# mainboard.net
KiCad netlist of a schematic drawn in EAGLE
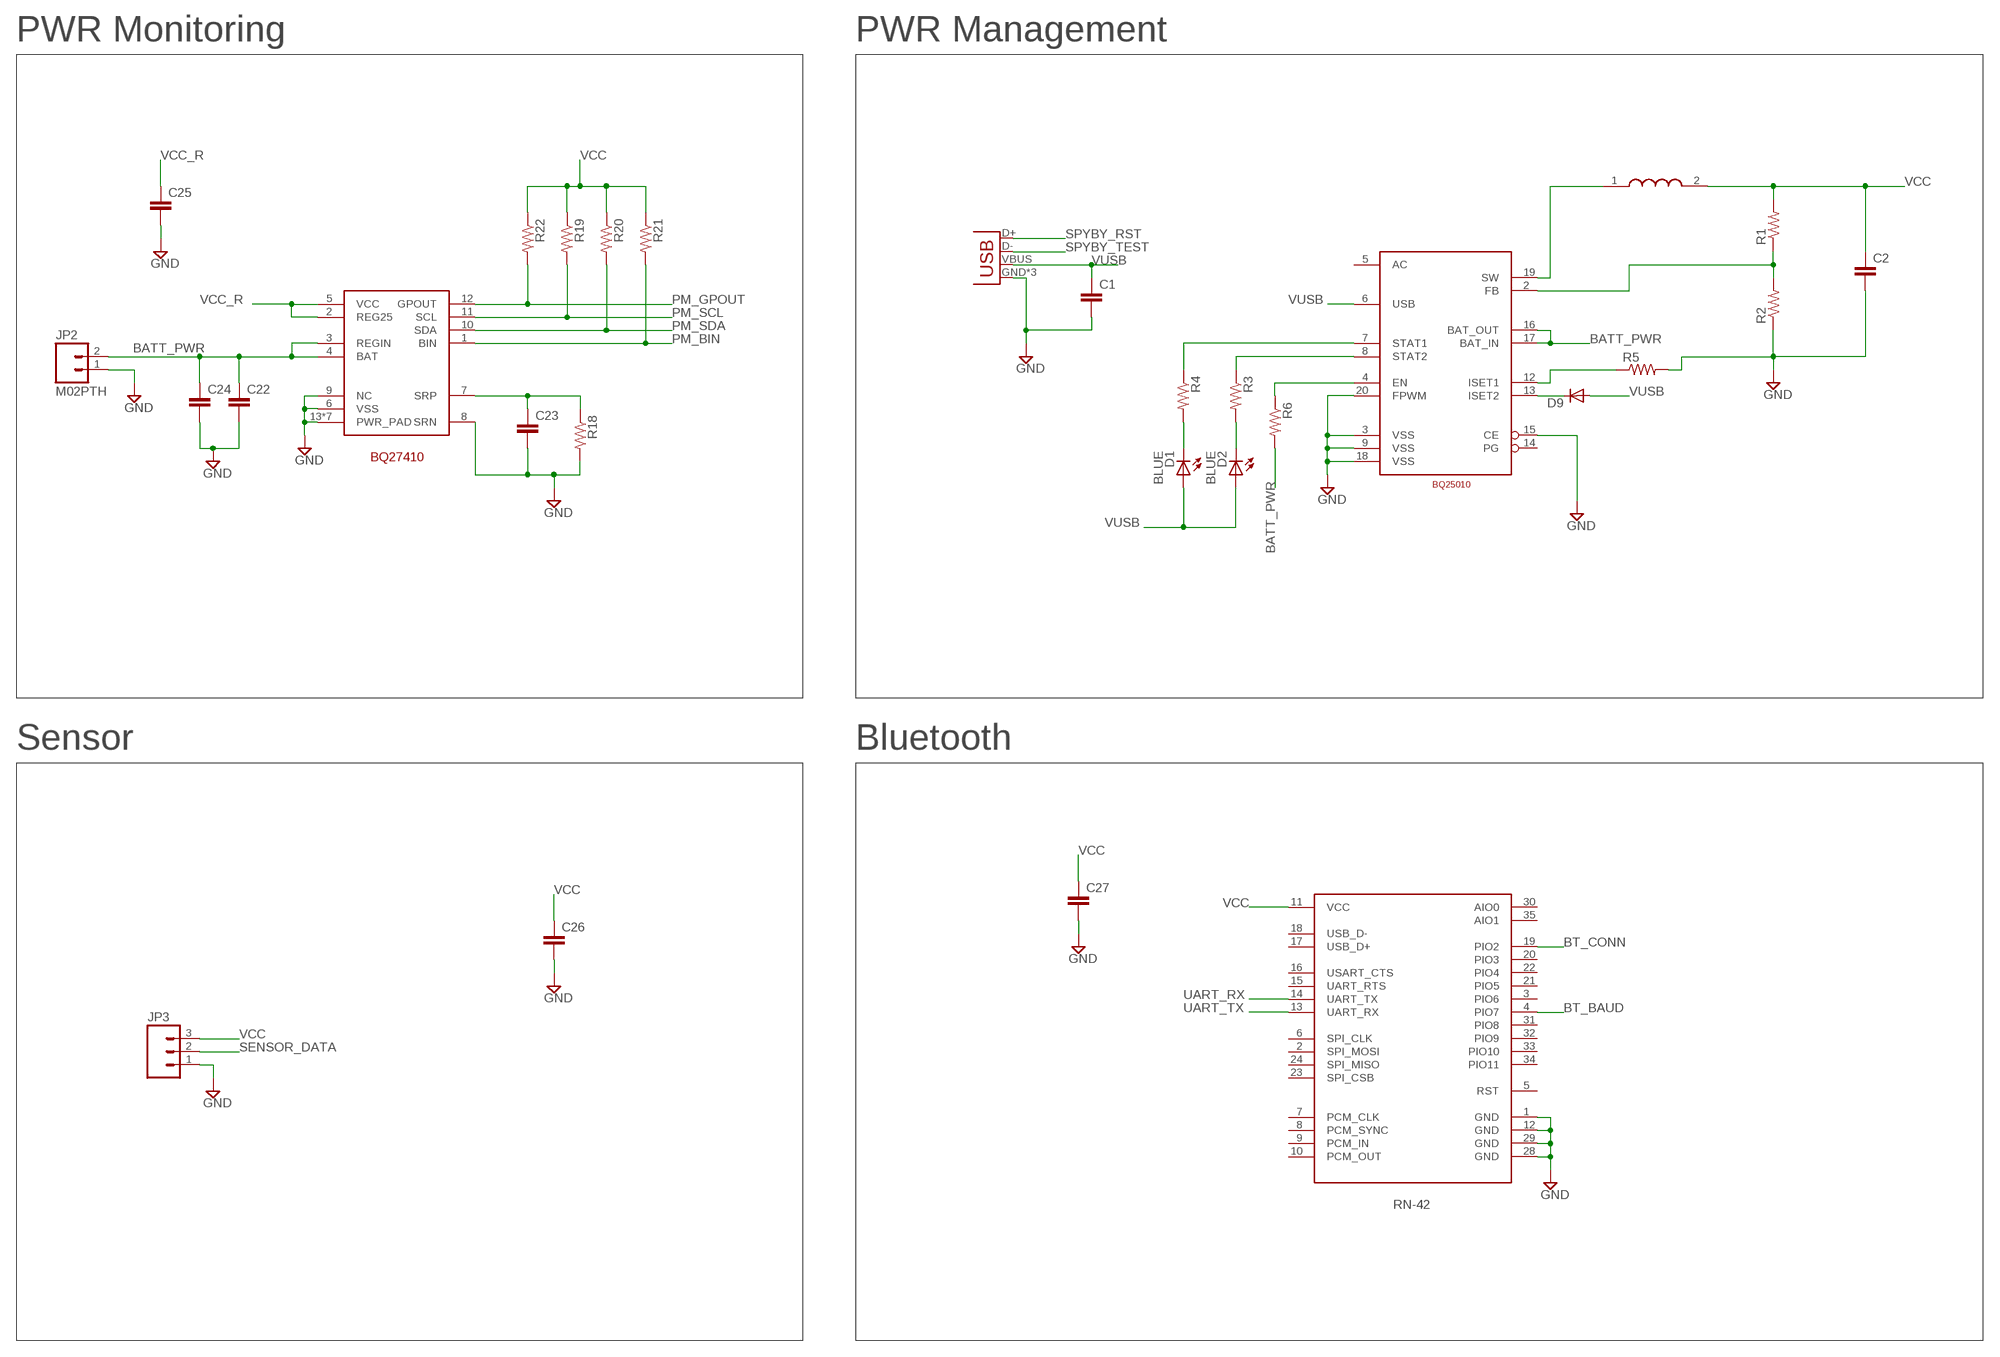
[diagram p0: schematic, sheet 1, part 1 of 2]
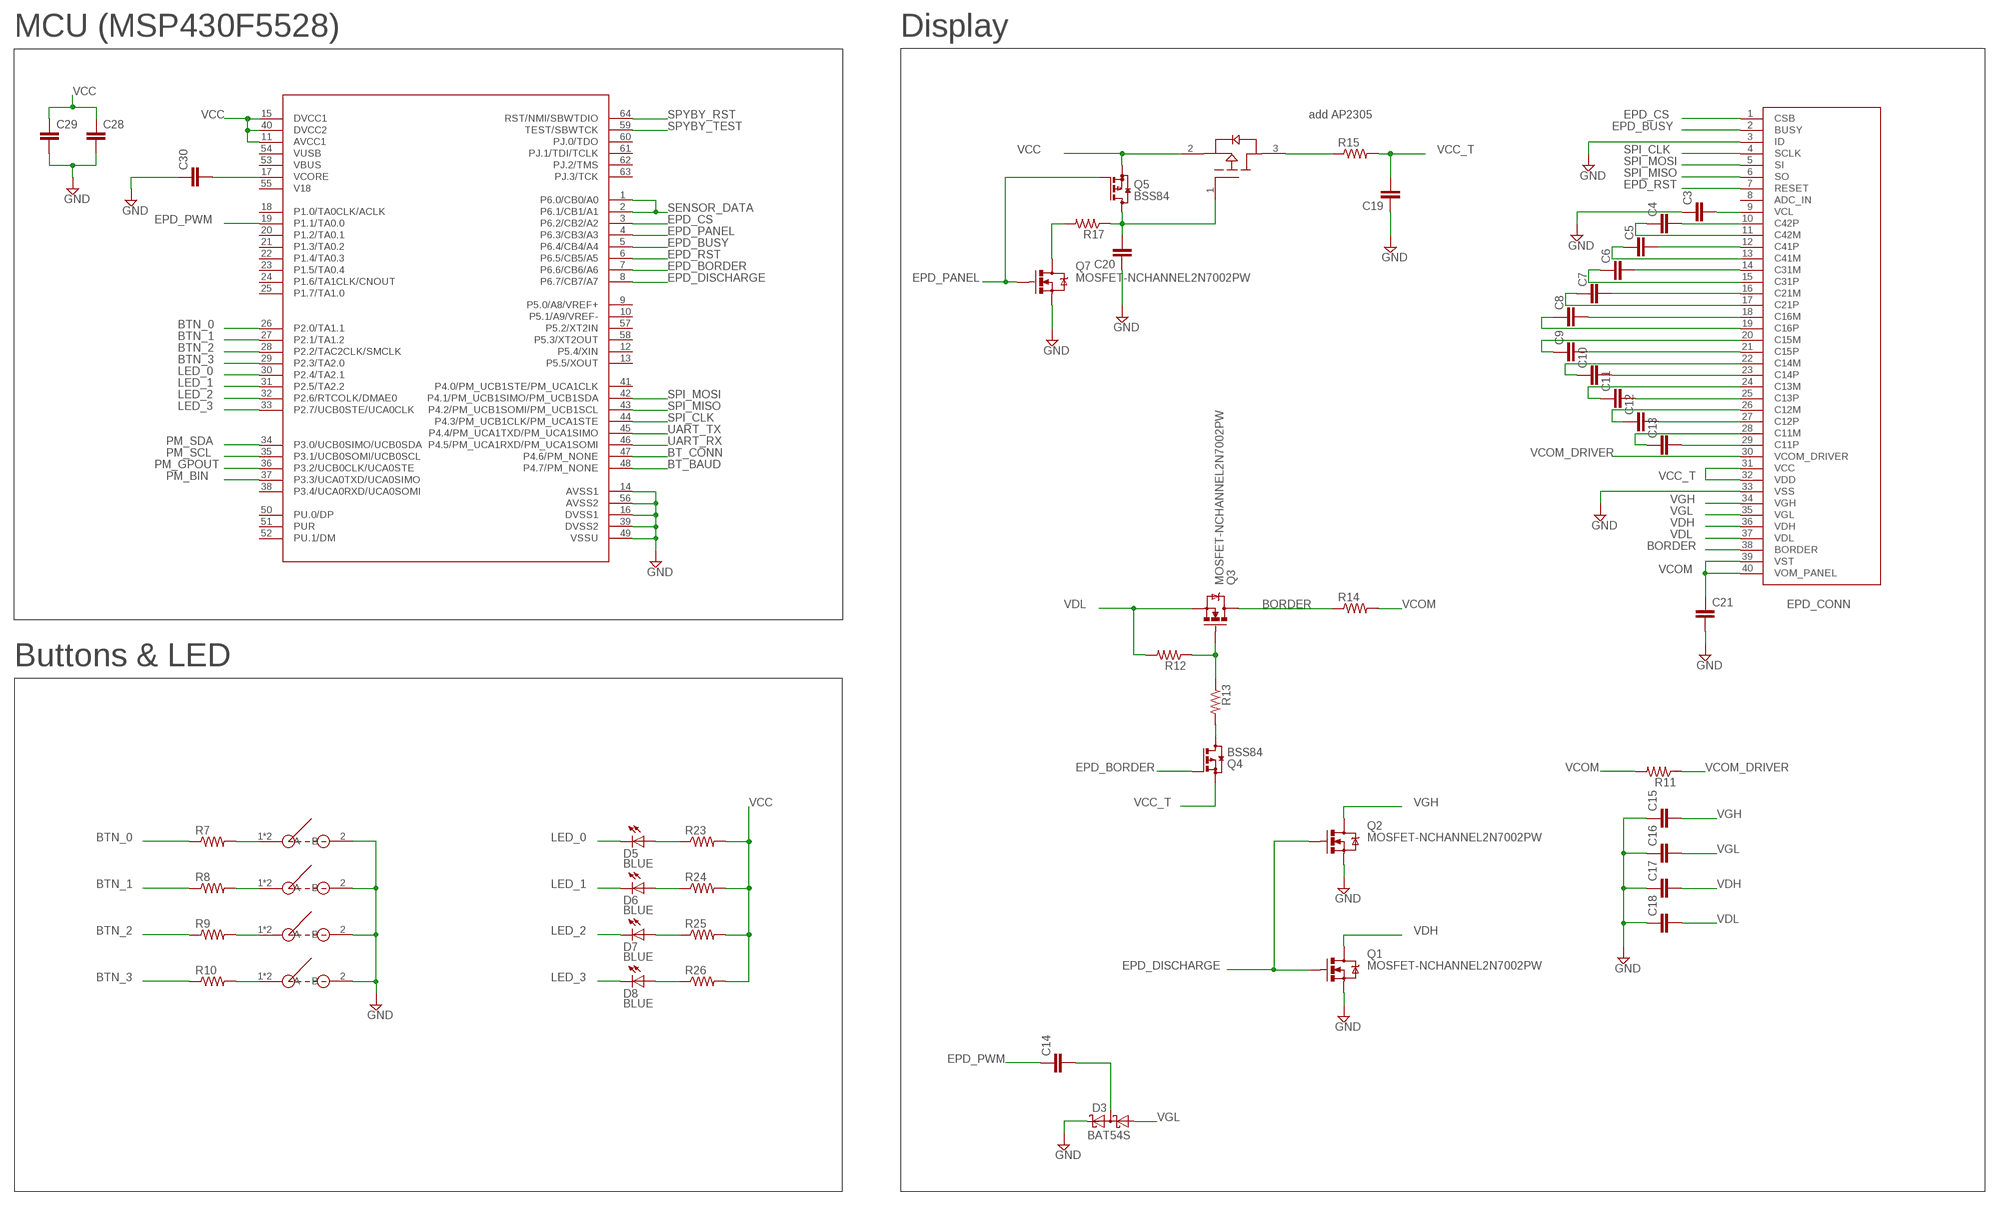
[diagram p1: schematic, sheet 1, part 2 of 2]

(export (version "E")
  (design (tool "Eeschema 10.0.6"))
  (components
    (comp (ref "C1")
      (value "CAP0402-CAP")
      (footprint "eagle-import:0402-CAP")
      (libsource (lib "eagle-import") (part "CAP0402-CAP"))
    )
    (comp (ref "C2")
      (value "CAP0402-CAP")
      (footprint "eagle-import:0402-CAP")
      (libsource (lib "eagle-import") (part "CAP0402-CAP"))
    )
    (comp (ref "C3")
      (value "CAP0402-CAP")
      (footprint "eagle-import:0402-CAP")
      (libsource (lib "eagle-import") (part "CAP0402-CAP"))
    )
    (comp (ref "C4")
      (value "CAP0402-CAP")
      (footprint "eagle-import:0402-CAP")
      (libsource (lib "eagle-import") (part "CAP0402-CAP"))
    )
    (comp (ref "C5")
      (value "CAP0402-CAP")
      (footprint "eagle-import:0402-CAP")
      (libsource (lib "eagle-import") (part "CAP0402-CAP"))
    )
    (comp (ref "C6")
      (value "CAP0402-CAP")
      (footprint "eagle-import:0402-CAP")
      (libsource (lib "eagle-import") (part "CAP0402-CAP"))
    )
    (comp (ref "C7")
      (value "CAP0402-CAP")
      (footprint "eagle-import:0402-CAP")
      (libsource (lib "eagle-import") (part "CAP0402-CAP"))
    )
    (comp (ref "C8")
      (value "CAP0402-CAP")
      (footprint "eagle-import:0402-CAP")
      (libsource (lib "eagle-import") (part "CAP0402-CAP"))
    )
    (comp (ref "C9")
      (value "CAP0402-CAP")
      (footprint "eagle-import:0402-CAP")
      (libsource (lib "eagle-import") (part "CAP0402-CAP"))
    )
    (comp (ref "C10")
      (value "CAP0402-CAP")
      (footprint "eagle-import:0402-CAP")
      (libsource (lib "eagle-import") (part "CAP0402-CAP"))
    )
    (comp (ref "C11")
      (value "CAP0402-CAP")
      (footprint "eagle-import:0402-CAP")
      (libsource (lib "eagle-import") (part "CAP0402-CAP"))
    )
    (comp (ref "C12")
      (value "CAP0402-CAP")
      (footprint "eagle-import:0402-CAP")
      (libsource (lib "eagle-import") (part "CAP0402-CAP"))
    )
    (comp (ref "C13")
      (value "CAP0402-CAP")
      (footprint "eagle-import:0402-CAP")
      (libsource (lib "eagle-import") (part "CAP0402-CAP"))
    )
    (comp (ref "C14")
      (value "CAP0402-CAP")
      (footprint "eagle-import:0402-CAP")
      (libsource (lib "eagle-import") (part "CAP0402-CAP"))
    )
    (comp (ref "C15")
      (value "CAP0402-CAP")
      (footprint "eagle-import:0402-CAP")
      (libsource (lib "eagle-import") (part "CAP0402-CAP"))
    )
    (comp (ref "C16")
      (value "CAP0402-CAP")
      (footprint "eagle-import:0402-CAP")
      (libsource (lib "eagle-import") (part "CAP0402-CAP"))
    )
    (comp (ref "C17")
      (value "CAP0402-CAP")
      (footprint "eagle-import:0402-CAP")
      (libsource (lib "eagle-import") (part "CAP0402-CAP"))
    )
    (comp (ref "C18")
      (value "CAP0402-CAP")
      (footprint "eagle-import:0402-CAP")
      (libsource (lib "eagle-import") (part "CAP0402-CAP"))
    )
    (comp (ref "C19")
      (value "CAP0402-CAP")
      (footprint "eagle-import:0402-CAP")
      (libsource (lib "eagle-import") (part "CAP0402-CAP"))
    )
    (comp (ref "C20")
      (value "CAP0402-CAP")
      (footprint "eagle-import:0402-CAP")
      (libsource (lib "eagle-import") (part "CAP0402-CAP"))
    )
    (comp (ref "C21")
      (value "CAP0402-CAP")
      (footprint "eagle-import:0402-CAP")
      (libsource (lib "eagle-import") (part "CAP0402-CAP"))
    )
    (comp (ref "C22")
      (value "CAP0402-CAP")
      (footprint "eagle-import:0402-CAP")
      (libsource (lib "eagle-import") (part "CAP0402-CAP"))
    )
    (comp (ref "C23")
      (value "CAP0402-CAP")
      (footprint "eagle-import:0402-CAP")
      (libsource (lib "eagle-import") (part "CAP0402-CAP"))
    )
    (comp (ref "C24")
      (value "CAP0402-CAP")
      (footprint "eagle-import:0402-CAP")
      (libsource (lib "eagle-import") (part "CAP0402-CAP"))
    )
    (comp (ref "C25")
      (value "CAP0402-CAP")
      (footprint "eagle-import:0402-CAP")
      (libsource (lib "eagle-import") (part "CAP0402-CAP"))
    )
    (comp (ref "C26")
      (value "CAP0402-CAP")
      (footprint "eagle-import:0402-CAP")
      (libsource (lib "eagle-import") (part "CAP0402-CAP"))
    )
    (comp (ref "C27")
      (value "CAP0402-CAP")
      (footprint "eagle-import:0402-CAP")
      (libsource (lib "eagle-import") (part "CAP0402-CAP"))
    )
    (comp (ref "C28")
      (value "CAP0402-CAP")
      (footprint "eagle-import:0402-CAP")
      (libsource (lib "eagle-import") (part "CAP0402-CAP"))
    )
    (comp (ref "C29")
      (value "CAP0402-CAP")
      (footprint "eagle-import:0402-CAP")
      (libsource (lib "eagle-import") (part "CAP0402-CAP"))
    )
    (comp (ref "C30")
      (value "CAP0402-CAP")
      (footprint "eagle-import:0402-CAP")
      (libsource (lib "eagle-import") (part "CAP0402-CAP"))
    )
    (comp (ref "D1")
      (value "BLUE")
      (footprint "eagle-import:LED-0603")
      (libsource (lib "eagle-import") (part "LED-BLUE0603"))
    )
    (comp (ref "D2")
      (value "BLUE")
      (footprint "eagle-import:LED-0603")
      (libsource (lib "eagle-import") (part "LED-BLUE0603"))
    )
    (comp (ref "D3")
      (value "BAT54S")
      (footprint "eagle-import:SOT23")
      (libsource (lib "eagle-import") (part "BAT54S"))
    )
    (comp (ref "D5")
      (value "BLUE")
      (footprint "eagle-import:LED-0603")
      (libsource (lib "eagle-import") (part "LED-BLUE0603"))
    )
    (comp (ref "D6")
      (value "BLUE")
      (footprint "eagle-import:LED-0603")
      (libsource (lib "eagle-import") (part "LED-BLUE0603"))
    )
    (comp (ref "D7")
      (value "BLUE")
      (footprint "eagle-import:LED-0603")
      (libsource (lib "eagle-import") (part "LED-BLUE0603"))
    )
    (comp (ref "D8")
      (value "BLUE")
      (footprint "eagle-import:LED-0603")
      (libsource (lib "eagle-import") (part "LED-BLUE0603"))
    )
    (comp (ref "D9")
      (value "DIODESOD523")
      (footprint "eagle-import:SOD523")
      (libsource (lib "eagle-import") (part "DIODESOD523"))
    )
    (comp (ref "JP1")
      (value "USB-MICROB")
      (footprint "eagle-import:USB-MICROB")
      (libsource (lib "eagle-import") (part "USB-MICROB"))
    )
    (comp (ref "JP2")
      (value "M02PTH")
      (footprint "eagle-import:1X02")
      (libsource (lib "eagle-import") (part "M02PTH"))
    )
    (comp (ref "JP3")
      (value "M03PTH")
      (footprint "eagle-import:1X03")
      (libsource (lib "eagle-import") (part "M03PTH"))
    )
    (comp (ref "Q1")
      (value "MOSFET-NCHANNEL2N7002PW")
      (footprint "eagle-import:SOT323")
      (libsource (lib "eagle-import") (part "MOSFET-NCHANNEL2N7002PW"))
    )
    (comp (ref "Q2")
      (value "MOSFET-NCHANNEL2N7002PW")
      (footprint "eagle-import:SOT323")
      (libsource (lib "eagle-import") (part "MOSFET-NCHANNEL2N7002PW"))
    )
    (comp (ref "Q3")
      (value "MOSFET-NCHANNEL2N7002PW")
      (footprint "eagle-import:SOT323")
      (libsource (lib "eagle-import") (part "MOSFET-NCHANNEL2N7002PW"))
    )
    (comp (ref "Q4")
      (value "BSS84")
      (footprint "eagle-import:SOT23")
      (libsource (lib "eagle-import") (part "BSS84"))
    )
    (comp (ref "Q5")
      (value "BSS84")
      (footprint "eagle-import:SOT23")
      (libsource (lib "eagle-import") (part "BSS84"))
    )
    (comp (ref "Q7")
      (value "MOSFET-NCHANNEL2N7002PW")
      (footprint "eagle-import:SOT323")
      (libsource (lib "eagle-import") (part "MOSFET-NCHANNEL2N7002PW"))
    )
    (comp (ref "R1")
      (value "RESISTOR0402-RES")
      (footprint "eagle-import:0402-RES")
      (libsource (lib "eagle-import") (part "RESISTOR0402-RES"))
    )
    (comp (ref "R2")
      (value "RESISTOR0402-RES")
      (footprint "eagle-import:0402-RES")
      (libsource (lib "eagle-import") (part "RESISTOR0402-RES"))
    )
    (comp (ref "R3")
      (value "RESISTOR0402-RES")
      (footprint "eagle-import:0402-RES")
      (libsource (lib "eagle-import") (part "RESISTOR0402-RES"))
    )
    (comp (ref "R4")
      (value "RESISTOR0402-RES")
      (footprint "eagle-import:0402-RES")
      (libsource (lib "eagle-import") (part "RESISTOR0402-RES"))
    )
    (comp (ref "R5")
      (value "RESISTOR0402-RES")
      (footprint "eagle-import:0402-RES")
      (libsource (lib "eagle-import") (part "RESISTOR0402-RES"))
    )
    (comp (ref "R6")
      (value "RESISTOR0402-RES")
      (footprint "eagle-import:0402-RES")
      (libsource (lib "eagle-import") (part "RESISTOR0402-RES"))
    )
    (comp (ref "R7")
      (value "RESISTOR0402-RES")
      (footprint "eagle-import:0402-RES")
      (libsource (lib "eagle-import") (part "RESISTOR0402-RES"))
    )
    (comp (ref "R8")
      (value "RESISTOR0402-RES")
      (footprint "eagle-import:0402-RES")
      (libsource (lib "eagle-import") (part "RESISTOR0402-RES"))
    )
    (comp (ref "R9")
      (value "RESISTOR0402-RES")
      (footprint "eagle-import:0402-RES")
      (libsource (lib "eagle-import") (part "RESISTOR0402-RES"))
    )
    (comp (ref "R10")
      (value "RESISTOR0402-RES")
      (footprint "eagle-import:0402-RES")
      (libsource (lib "eagle-import") (part "RESISTOR0402-RES"))
    )
    (comp (ref "R11")
      (value "RESISTOR0402-RES")
      (footprint "eagle-import:0402-RES")
      (libsource (lib "eagle-import") (part "RESISTOR0402-RES"))
    )
    (comp (ref "R12")
      (value "RESISTOR0402-RES")
      (footprint "eagle-import:0402-RES")
      (libsource (lib "eagle-import") (part "RESISTOR0402-RES"))
    )
    (comp (ref "R13")
      (value "RESISTOR0402-RES")
      (footprint "eagle-import:0402-RES")
      (libsource (lib "eagle-import") (part "RESISTOR0402-RES"))
    )
    (comp (ref "R14")
      (value "RESISTOR0402-RES")
      (footprint "eagle-import:0402-RES")
      (libsource (lib "eagle-import") (part "RESISTOR0402-RES"))
    )
    (comp (ref "R15")
      (value "RESISTOR0402-RES")
      (footprint "eagle-import:0402-RES")
      (libsource (lib "eagle-import") (part "RESISTOR0402-RES"))
    )
    (comp (ref "R17")
      (value "RESISTOR0402-RES")
      (footprint "eagle-import:0402-RES")
      (libsource (lib "eagle-import") (part "RESISTOR0402-RES"))
    )
    (comp (ref "R18")
      (value "RESISTOR0402-RES")
      (footprint "eagle-import:0402-RES")
      (libsource (lib "eagle-import") (part "RESISTOR0402-RES"))
    )
    (comp (ref "R19")
      (value "RESISTOR0402-RES")
      (footprint "eagle-import:0402-RES")
      (libsource (lib "eagle-import") (part "RESISTOR0402-RES"))
    )
    (comp (ref "R20")
      (value "RESISTOR0402-RES")
      (footprint "eagle-import:0402-RES")
      (libsource (lib "eagle-import") (part "RESISTOR0402-RES"))
    )
    (comp (ref "R21")
      (value "RESISTOR0402-RES")
      (footprint "eagle-import:0402-RES")
      (libsource (lib "eagle-import") (part "RESISTOR0402-RES"))
    )
    (comp (ref "R22")
      (value "RESISTOR0402-RES")
      (footprint "eagle-import:0402-RES")
      (libsource (lib "eagle-import") (part "RESISTOR0402-RES"))
    )
    (comp (ref "R23")
      (value "RESISTOR0402-RES")
      (footprint "eagle-import:0402-RES")
      (libsource (lib "eagle-import") (part "RESISTOR0402-RES"))
    )
    (comp (ref "R24")
      (value "RESISTOR0402-RES")
      (footprint "eagle-import:0402-RES")
      (libsource (lib "eagle-import") (part "RESISTOR0402-RES"))
    )
    (comp (ref "R25")
      (value "RESISTOR0402-RES")
      (footprint "eagle-import:0402-RES")
      (libsource (lib "eagle-import") (part "RESISTOR0402-RES"))
    )
    (comp (ref "R26")
      (value "RESISTOR0402-RES")
      (footprint "eagle-import:0402-RES")
      (libsource (lib "eagle-import") (part "RESISTOR0402-RES"))
    )
    (comp (ref "U$1")
      (value "MSP430F5528")
      (footprint "eagle-import:VQFN_RGC_64PIN")
      (libsource (lib "eagle-import") (part "MSP430F5528"))
    )
    (comp (ref "U$2")
      (value "RN-42")
      (footprint "eagle-import:RN-42")
      (libsource (lib "eagle-import") (part "RN-42"))
    )
    (comp (ref "U$3")
      (value "BQ25010")
      (footprint "eagle-import:VQFN_RHL_20PIN")
      (libsource (lib "eagle-import") (part "BQ25010"))
    )
    (comp (ref "U$4")
      (value "EVP-AEDB2A")
      (footprint "eagle-import:EVP-AEDB2A")
      (libsource (lib "eagle-import") (part "EVP-AEDB2A"))
    )
    (comp (ref "U$5")
      (value "EVP-AEDB2A")
      (footprint "eagle-import:EVP-AEDB2A")
      (libsource (lib "eagle-import") (part "EVP-AEDB2A"))
    )
    (comp (ref "U$6")
      (value "EVP-AEDB2A")
      (footprint "eagle-import:EVP-AEDB2A")
      (libsource (lib "eagle-import") (part "EVP-AEDB2A"))
    )
    (comp (ref "U$7")
      (value "EVP-AEDB2A")
      (footprint "eagle-import:EVP-AEDB2A")
      (libsource (lib "eagle-import") (part "EVP-AEDB2A"))
    )
    (comp (ref "U$8")
      (value "FH12-40S-0.5SH")
      (footprint "eagle-import:FH12-40S-0.5SH")
      (libsource (lib "eagle-import") (part "FH12-40S-0.5SH"))
    )
    (comp (ref "U$9")
      (value "BQ27410")
      (footprint "eagle-import:SON_DRZ_12PIN")
      (libsource (lib "eagle-import") (part "BQ27410"))
    )
    (comp (ref "U$10")
      (value "DMG2305UX")
      (footprint "eagle-import:SOT23")
      (libsource (lib "eagle-import") (part "DMG2305UX"))
    )
    (comp (ref "U$11")
      (value "ASPI-0428S-100M-T")
      (footprint "eagle-import:ASPI_0428S-100M-T")
      (libsource (lib "eagle-import") (part "ASPI-0428S-100M-T"))
    )
  )
  (nets
    (net (code "1") (name "/BATT_PWR") (class "Default")
      (node (ref "C22") (pin "1") (pinfunction "1_1") (pintype "passive"))
      (node (ref "C24") (pin "1") (pinfunction "1_1") (pintype "passive"))
      (node (ref "JP2") (pin "2") (pinfunction "2_2") (pintype "passive"))
      (node (ref "R6") (pin "2") (pinfunction "2_2") (pintype "passive"))
      (node (ref "U$3") (pin "16") (pinfunction "BAT_OUT_16") (pintype "bidirectional"))
      (node (ref "U$3") (pin "17") (pinfunction "BAT_IN_17") (pintype "bidirectional"))
      (node (ref "U$9") (pin "3") (pinfunction "REGIN_3") (pintype "bidirectional"))
      (node (ref "U$9") (pin "4") (pinfunction "BAT_4") (pintype "bidirectional"))
    )
    (net (code "2") (name "/BORDER") (class "Default")
      (node (ref "Q3") (pin "3") (pinfunction "D_3") (pintype "passive"))
      (node (ref "R14") (pin "1") (pinfunction "1_1") (pintype "passive"))
      (node (ref "U$8") (pin "38") (pinfunction "BORDER_38") (pintype "bidirectional"))
    )
    (net (code "3") (name "/BTN_0") (class "Default")
      (node (ref "R7") (pin "1") (pinfunction "1_1") (pintype "passive"))
      (node (ref "U$1") (pin "26") (pinfunction "P2.0/TA1.1_26") (pintype "bidirectional"))
    )
    (net (code "4") (name "/BTN_1") (class "Default")
      (node (ref "R8") (pin "1") (pinfunction "1_1") (pintype "passive"))
      (node (ref "U$1") (pin "27") (pinfunction "P2.1/TA1.2_27") (pintype "bidirectional"))
    )
    (net (code "5") (name "/BTN_2") (class "Default")
      (node (ref "R9") (pin "1") (pinfunction "1_1") (pintype "passive"))
      (node (ref "U$1") (pin "28") (pinfunction "P2.2/TAC2CLK/SMCLK_28") (pintype "bidirectional"))
    )
    (net (code "6") (name "/BTN_3") (class "Default")
      (node (ref "R10") (pin "1") (pinfunction "1_1") (pintype "passive"))
      (node (ref "U$1") (pin "29") (pinfunction "P2.3/TA2.0_29") (pintype "bidirectional"))
    )
    (net (code "7") (name "/BT_BAUD") (class "Default")
      (node (ref "U$1") (pin "48") (pinfunction "P4.7/PM_NONE_48") (pintype "bidirectional"))
      (node (ref "U$2") (pin "4") (pinfunction "PIO7_4") (pintype "bidirectional"))
    )
    (net (code "8") (name "/BT_CONN") (class "Default")
      (node (ref "U$1") (pin "47") (pinfunction "P4.6/PM_NONE_47") (pintype "bidirectional"))
      (node (ref "U$2") (pin "19") (pinfunction "PIO2_19") (pintype "bidirectional"))
    )
    (net (code "9") (name "/EPD_BORDER") (class "Default")
      (node (ref "Q4") (pin "1") (pinfunction "G_1") (pintype "passive"))
      (node (ref "U$1") (pin "7") (pinfunction "P6.6/CB6/A6_7") (pintype "bidirectional"))
    )
    (net (code "10") (name "/EPD_BUSY") (class "Default")
      (node (ref "U$1") (pin "5") (pinfunction "P6.4/CB4/A4_5") (pintype "bidirectional"))
      (node (ref "U$8") (pin "2") (pinfunction "BUSY_2") (pintype "bidirectional"))
    )
    (net (code "11") (name "/EPD_CS") (class "Default")
      (node (ref "U$1") (pin "3") (pinfunction "P6.2/CB2/A2_3") (pintype "bidirectional"))
      (node (ref "U$8") (pin "1") (pinfunction "CSB_1") (pintype "bidirectional"))
    )
    (net (code "12") (name "/EPD_DISCHARGE") (class "Default")
      (node (ref "Q1") (pin "1") (pinfunction "G_1") (pintype "passive"))
      (node (ref "Q2") (pin "1") (pinfunction "G_1") (pintype "passive"))
      (node (ref "U$1") (pin "8") (pinfunction "P6.7/CB7/A7_8") (pintype "bidirectional"))
    )
    (net (code "13") (name "/EPD_PANEL") (class "Default")
      (node (ref "Q5") (pin "1") (pinfunction "G_1") (pintype "passive"))
      (node (ref "Q7") (pin "1") (pinfunction "G_1") (pintype "passive"))
      (node (ref "U$1") (pin "4") (pinfunction "P6.3/CB3/A3_4") (pintype "bidirectional"))
    )
    (net (code "14") (name "/EPD_PWM") (class "Default")
      (node (ref "C14") (pin "1") (pinfunction "1_1") (pintype "passive"))
      (node (ref "U$1") (pin "19") (pinfunction "P1.1/TA0.0_19") (pintype "bidirectional"))
    )
    (net (code "15") (name "/EPD_RST") (class "Default")
      (node (ref "U$1") (pin "6") (pinfunction "P6.5/CB5/A5_6") (pintype "bidirectional"))
      (node (ref "U$8") (pin "7") (pinfunction "RESET_7") (pintype "bidirectional"))
    )
    (net (code "16") (name "/LED_0") (class "Default")
      (node (ref "D5") (pin "C") (pinfunction "C_C") (pintype "passive"))
      (node (ref "U$1") (pin "30") (pinfunction "P2.4/TA2.1_30") (pintype "bidirectional"))
    )
    (net (code "17") (name "/LED_1") (class "Default")
      (node (ref "D6") (pin "C") (pinfunction "C_C") (pintype "passive"))
      (node (ref "U$1") (pin "31") (pinfunction "P2.5/TA2.2_31") (pintype "bidirectional"))
    )
    (net (code "18") (name "/LED_2") (class "Default")
      (node (ref "D7") (pin "C") (pinfunction "C_C") (pintype "passive"))
      (node (ref "U$1") (pin "32") (pinfunction "P2.6/RTCOLK/DMAE0_32") (pintype "bidirectional"))
    )
    (net (code "19") (name "/LED_3") (class "Default")
      (node (ref "D8") (pin "C") (pinfunction "C_C") (pintype "passive"))
      (node (ref "U$1") (pin "33") (pinfunction "P2.7/UCB0STE/UCA0CLK_33") (pintype "bidirectional"))
    )
    (net (code "20") (name "/PM_BIN") (class "Default")
      (node (ref "R21") (pin "2") (pinfunction "2_2") (pintype "passive"))
      (node (ref "U$1") (pin "37") (pinfunction "P3.3/UCA0TXD/UCA0SIMO_37") (pintype "bidirectional"))
      (node (ref "U$9") (pin "1") (pinfunction "BIN_1") (pintype "bidirectional"))
    )
    (net (code "21") (name "/PM_GPOUT") (class "Default")
      (node (ref "R22") (pin "2") (pinfunction "2_2") (pintype "passive"))
      (node (ref "U$1") (pin "36") (pinfunction "P3.2/UCB0CLK/UCA0STE_36") (pintype "bidirectional"))
      (node (ref "U$9") (pin "12") (pinfunction "GPOUT_12") (pintype "bidirectional"))
    )
    (net (code "22") (name "/PM_SCL") (class "Default")
      (node (ref "R19") (pin "2") (pinfunction "2_2") (pintype "passive"))
      (node (ref "U$1") (pin "35") (pinfunction "P3.1/UCB0SOMI/UCB0SCL_35") (pintype "bidirectional"))
      (node (ref "U$9") (pin "11") (pinfunction "SCL_11") (pintype "bidirectional"))
    )
    (net (code "23") (name "/PM_SDA") (class "Default")
      (node (ref "R20") (pin "2") (pinfunction "2_2") (pintype "passive"))
      (node (ref "U$1") (pin "34") (pinfunction "P3.0/UCB0SIMO/UCB0SDA_34") (pintype "bidirectional"))
      (node (ref "U$9") (pin "10") (pinfunction "SDA_10") (pintype "bidirectional"))
    )
    (net (code "24") (name "/SENSOR_DATA") (class "Default")
      (node (ref "JP3") (pin "2") (pinfunction "2_2") (pintype "passive"))
      (node (ref "U$1") (pin "1") (pinfunction "P6.0/CB0/A0_1") (pintype "bidirectional"))
      (node (ref "U$1") (pin "2") (pinfunction "P6.1/CB1/A1_2") (pintype "bidirectional"))
    )
    (net (code "25") (name "/SPI_CLK") (class "Default")
      (node (ref "U$1") (pin "44") (pinfunction "P4.3/PM_UCB1CLK/PM_UCA1STE_44") (pintype "bidirectional"))
      (node (ref "U$8") (pin "4") (pinfunction "SCLK_4") (pintype "bidirectional"))
    )
    (net (code "26") (name "/SPI_MISO") (class "Default")
      (node (ref "U$1") (pin "43") (pinfunction "P4.2/PM_UCB1SOMI/PM_UCB1SCL_43") (pintype "bidirectional"))
      (node (ref "U$8") (pin "6") (pinfunction "SO_6") (pintype "bidirectional"))
    )
    (net (code "27") (name "/SPI_MOSI") (class "Default")
      (node (ref "U$1") (pin "42") (pinfunction "P4.1/PM_UCB1SIMO/PM_UCB1SDA_42") (pintype "bidirectional"))
      (node (ref "U$8") (pin "5") (pinfunction "SI_5") (pintype "bidirectional"))
    )
    (net (code "28") (name "/SPYBY_RST") (class "Default")
      (node (ref "JP1") (pin "D+") (pinfunction "D+_D+") (pintype "bidirectional"))
      (node (ref "U$1") (pin "64") (pinfunction "RST/NMI/SBWTDIO_64") (pintype "bidirectional"))
    )
    (net (code "29") (name "/SPYBY_TEST") (class "Default")
      (node (ref "JP1") (pin "D-") (pinfunction "D-_D-") (pintype "bidirectional"))
      (node (ref "U$1") (pin "59") (pinfunction "TEST/SBWTCK_59") (pintype "bidirectional"))
    )
    (net (code "30") (name "/UART_RX") (class "Default")
      (node (ref "U$1") (pin "46") (pinfunction "P4.5/PM_UCA1RXD/PM_UCA1SOMI_46") (pintype "bidirectional"))
      (node (ref "U$2") (pin "14") (pinfunction "UART_TX_14") (pintype "bidirectional"))
    )
    (net (code "31") (name "/UART_TX") (class "Default")
      (node (ref "U$1") (pin "45") (pinfunction "P4.4/PM_UCA1TXD/PM_UCA1SIMO_45") (pintype "bidirectional"))
      (node (ref "U$2") (pin "13") (pinfunction "UART_RX_13") (pintype "bidirectional"))
    )
    (net (code "32") (name "/VCC") (class "Default")
      (node (ref "C2") (pin "1") (pinfunction "1_1") (pintype "passive"))
      (node (ref "C26") (pin "1") (pinfunction "1_1") (pintype "passive"))
      (node (ref "C27") (pin "1") (pinfunction "1_1") (pintype "passive"))
      (node (ref "C28") (pin "1") (pinfunction "1_1") (pintype "passive"))
      (node (ref "C29") (pin "1") (pinfunction "1_1") (pintype "passive"))
      (node (ref "JP3") (pin "3") (pinfunction "3_3") (pintype "passive"))
      (node (ref "Q5") (pin "2") (pinfunction "S_2") (pintype "passive"))
      (node (ref "R1") (pin "2") (pinfunction "2_2") (pintype "passive"))
      (node (ref "R19") (pin "1") (pinfunction "1_1") (pintype "passive"))
      (node (ref "R20") (pin "1") (pinfunction "1_1") (pintype "passive"))
      (node (ref "R21") (pin "1") (pinfunction "1_1") (pintype "passive"))
      (node (ref "R22") (pin "1") (pinfunction "1_1") (pintype "passive"))
      (node (ref "R23") (pin "2") (pinfunction "2_2") (pintype "passive"))
      (node (ref "R24") (pin "2") (pinfunction "2_2") (pintype "passive"))
      (node (ref "R25") (pin "2") (pinfunction "2_2") (pintype "passive"))
      (node (ref "R26") (pin "2") (pinfunction "2_2") (pintype "passive"))
      (node (ref "U$1") (pin "11") (pinfunction "AVCC1_11") (pintype "bidirectional"))
      (node (ref "U$1") (pin "15") (pinfunction "DVCC1_15") (pintype "bidirectional"))
      (node (ref "U$1") (pin "40") (pinfunction "DVCC2_40") (pintype "bidirectional"))
      (node (ref "U$10") (pin "2") (pinfunction "SOURCE_2") (pintype "bidirectional"))
      (node (ref "U$11") (pin "2") (pinfunction "P$2_2") (pintype "bidirectional"))
      (node (ref "U$2") (pin "11") (pinfunction "VCC_11") (pintype "bidirectional"))
    )
    (net (code "33") (name "/VCC_R") (class "Default")
      (node (ref "C25") (pin "1") (pinfunction "1_1") (pintype "passive"))
      (node (ref "U$9") (pin "2") (pinfunction "REG25_2") (pintype "bidirectional"))
      (node (ref "U$9") (pin "5") (pinfunction "VCC_5") (pintype "bidirectional"))
    )
    (net (code "34") (name "/VCC_T") (class "Default")
      (node (ref "C19") (pin "2") (pinfunction "2_2") (pintype "passive"))
      (node (ref "Q4") (pin "2") (pinfunction "S_2") (pintype "passive"))
      (node (ref "R15") (pin "2") (pinfunction "2_2") (pintype "passive"))
      (node (ref "U$8") (pin "31") (pinfunction "VCC_31") (pintype "bidirectional"))
      (node (ref "U$8") (pin "32") (pinfunction "VDD_32") (pintype "bidirectional"))
    )
    (net (code "35") (name "/VCOM") (class "Default")
      (node (ref "C21") (pin "1") (pinfunction "1_1") (pintype "passive"))
      (node (ref "R11") (pin "2") (pinfunction "2_2") (pintype "passive"))
      (node (ref "R14") (pin "2") (pinfunction "2_2") (pintype "passive"))
      (node (ref "U$8") (pin "39") (pinfunction "VST_39") (pintype "bidirectional"))
      (node (ref "U$8") (pin "40") (pinfunction "VOM_PANEL_40") (pintype "bidirectional"))
    )
    (net (code "36") (name "/VCOM_DRIVER") (class "Default")
      (node (ref "R11") (pin "1") (pinfunction "1_1") (pintype "passive"))
      (node (ref "U$8") (pin "30") (pinfunction "VCOM_DRIVER_30") (pintype "bidirectional"))
    )
    (net (code "37") (name "/VDH") (class "Default")
      (node (ref "C17") (pin "2") (pinfunction "2_2") (pintype "passive"))
      (node (ref "Q1") (pin "3") (pinfunction "D_3") (pintype "passive"))
      (node (ref "U$8") (pin "36") (pinfunction "VDH_36") (pintype "bidirectional"))
    )
    (net (code "38") (name "/VDL") (class "Default")
      (node (ref "C18") (pin "2") (pinfunction "2_2") (pintype "passive"))
      (node (ref "Q3") (pin "2") (pinfunction "S_2") (pintype "passive"))
      (node (ref "R12") (pin "2") (pinfunction "2_2") (pintype "passive"))
      (node (ref "U$8") (pin "37") (pinfunction "VDL_37") (pintype "bidirectional"))
    )
    (net (code "39") (name "/VGH") (class "Default")
      (node (ref "C15") (pin "2") (pinfunction "2_2") (pintype "passive"))
      (node (ref "Q2") (pin "3") (pinfunction "D_3") (pintype "passive"))
      (node (ref "U$8") (pin "34") (pinfunction "VGH_34") (pintype "bidirectional"))
    )
    (net (code "40") (name "/VGL") (class "Default")
      (node (ref "C16") (pin "2") (pinfunction "2_2") (pintype "passive"))
      (node (ref "D3") (pin "1") (pinfunction "A1_1") (pintype "passive"))
      (node (ref "U$8") (pin "35") (pinfunction "VGL_35") (pintype "bidirectional"))
    )
    (net (code "41") (name "/VUSB") (class "Default")
      (node (ref "C1") (pin "1") (pinfunction "1_1") (pintype "passive"))
      (node (ref "D1") (pin "A") (pinfunction "A_A") (pintype "passive"))
      (node (ref "D2") (pin "A") (pinfunction "A_A") (pintype "passive"))
      (node (ref "D9") (pin "A") (pinfunction "A_A") (pintype "passive"))
      (node (ref "JP1") (pin "VBUS") (pinfunction "VBUS_VBUS") (pintype "bidirectional"))
      (node (ref "U$3") (pin "6") (pinfunction "USB_6") (pintype "bidirectional"))
    )
    (net (code "42") (name "GND") (class "Default")
      (node (ref "C1") (pin "2") (pinfunction "2_2") (pintype "passive"))
      (node (ref "C15") (pin "1") (pinfunction "1_1") (pintype "passive"))
      (node (ref "C16") (pin "1") (pinfunction "1_1") (pintype "passive"))
      (node (ref "C17") (pin "1") (pinfunction "1_1") (pintype "passive"))
      (node (ref "C18") (pin "1") (pinfunction "1_1") (pintype "passive"))
      (node (ref "C19") (pin "1") (pinfunction "1_1") (pintype "passive"))
      (node (ref "C2") (pin "2") (pinfunction "2_2") (pintype "passive"))
      (node (ref "C20") (pin "1") (pinfunction "1_1") (pintype "passive"))
      (node (ref "C21") (pin "2") (pinfunction "2_2") (pintype "passive"))
      (node (ref "C22") (pin "2") (pinfunction "2_2") (pintype "passive"))
      (node (ref "C23") (pin "2") (pinfunction "2_2") (pintype "passive"))
      (node (ref "C24") (pin "2") (pinfunction "2_2") (pintype "passive"))
      (node (ref "C25") (pin "2") (pinfunction "2_2") (pintype "passive"))
      (node (ref "C26") (pin "2") (pinfunction "2_2") (pintype "passive"))
      (node (ref "C27") (pin "2") (pinfunction "2_2") (pintype "passive"))
      (node (ref "C28") (pin "2") (pinfunction "2_2") (pintype "passive"))
      (node (ref "C29") (pin "2") (pinfunction "2_2") (pintype "passive"))
      (node (ref "C3") (pin "1") (pinfunction "1_1") (pintype "passive"))
      (node (ref "C30") (pin "1") (pinfunction "1_1") (pintype "passive"))
      (node (ref "D3") (pin "2") (pinfunction "C2_2") (pintype "passive"))
      (node (ref "JP1") (pin "GND") (pinfunction "GND_GND") (pintype "bidirectional"))
      (node (ref "JP1") (pin "MT1") (pinfunction "GND_MT1") (pintype "bidirectional"))
      (node (ref "JP1") (pin "MT2") (pinfunction "GND_MT2") (pintype "bidirectional"))
      (node (ref "JP2") (pin "1") (pinfunction "1_1") (pintype "passive"))
      (node (ref "JP3") (pin "1") (pinfunction "1_1") (pintype "passive"))
      (node (ref "Q1") (pin "2") (pinfunction "S_2") (pintype "passive"))
      (node (ref "Q2") (pin "2") (pinfunction "S_2") (pintype "passive"))
      (node (ref "Q7") (pin "2") (pinfunction "S_2") (pintype "passive"))
      (node (ref "R18") (pin "2") (pinfunction "2_2") (pintype "passive"))
      (node (ref "R2") (pin "1") (pinfunction "1_1") (pintype "passive"))
      (node (ref "R5") (pin "2") (pinfunction "2_2") (pintype "passive"))
      (node (ref "U$1") (pin "14") (pinfunction "AVSS1_14") (pintype "bidirectional"))
      (node (ref "U$1") (pin "16") (pinfunction "DVSS1_16") (pintype "bidirectional"))
      (node (ref "U$1") (pin "39") (pinfunction "DVSS2_39") (pintype "bidirectional"))
      (node (ref "U$1") (pin "49") (pinfunction "VSSU_49") (pintype "bidirectional"))
      (node (ref "U$1") (pin "56") (pinfunction "AVSS2_56") (pintype "bidirectional"))
      (node (ref "U$2") (pin "1") (pinfunction "GND_1") (pintype "bidirectional"))
      (node (ref "U$2") (pin "12") (pinfunction "GND_12") (pintype "bidirectional"))
      (node (ref "U$2") (pin "28") (pinfunction "GND_28") (pintype "bidirectional"))
      (node (ref "U$2") (pin "29") (pinfunction "GND_29") (pintype "bidirectional"))
      (node (ref "U$3") (pin "15") (pinfunction "CE_15") (pintype "bidirectional"))
      (node (ref "U$3") (pin "18") (pinfunction "VSS_18") (pintype "bidirectional"))
      (node (ref "U$3") (pin "20") (pinfunction "FPWM_20") (pintype "bidirectional"))
      (node (ref "U$3") (pin "3") (pinfunction "VSS_3") (pintype "bidirectional"))
      (node (ref "U$3") (pin "9") (pinfunction "VSS_9") (pintype "bidirectional"))
      (node (ref "U$4") (pin "2") (pinfunction "B_2") (pintype "bidirectional"))
      (node (ref "U$5") (pin "2") (pinfunction "B_2") (pintype "bidirectional"))
      (node (ref "U$6") (pin "2") (pinfunction "B_2") (pintype "bidirectional"))
      (node (ref "U$7") (pin "2") (pinfunction "B_2") (pintype "bidirectional"))
      (node (ref "U$8") (pin "3") (pinfunction "ID_3") (pintype "bidirectional"))
      (node (ref "U$8") (pin "33") (pinfunction "VSS_33") (pintype "bidirectional"))
      (node (ref "U$9") (pin "13") (pinfunction "PWR_PAD_13") (pintype "bidirectional"))
      (node (ref "U$9") (pin "6") (pinfunction "VSS_6") (pintype "bidirectional"))
      (node (ref "U$9") (pin "8") (pinfunction "SRN_8") (pintype "bidirectional"))
      (node (ref "U$9") (pin "9") (pinfunction "NC_9") (pintype "bidirectional"))
      (node (ref "U$9") (pin "P$15") (pinfunction "PWR_PAD_P$15") (pintype "bidirectional"))
      (node (ref "U$9") (pin "P$16") (pinfunction "PWR_PAD_P$16") (pintype "bidirectional"))
      (node (ref "U$9") (pin "P$17") (pinfunction "PWR_PAD_P$17") (pintype "bidirectional"))
      (node (ref "U$9") (pin "P$18") (pinfunction "PWR_PAD_P$18") (pintype "bidirectional"))
      (node (ref "U$9") (pin "P$19") (pinfunction "PWR_PAD_P$19") (pintype "bidirectional"))
      (node (ref "U$9") (pin "P$20") (pinfunction "PWR_PAD_P$20") (pintype "bidirectional"))
    )
    (net (code "43") (name "Net-(D1-PadC)") (class "Default")
      (node (ref "D1") (pin "C") (pinfunction "C_C") (pintype "passive"))
      (node (ref "R4") (pin "2") (pinfunction "2_2") (pintype "passive"))
    )
    (net (code "44") (name "Net-(D2-PadC)") (class "Default")
      (node (ref "D2") (pin "C") (pinfunction "C_C") (pintype "passive"))
      (node (ref "R3") (pin "2") (pinfunction "2_2") (pintype "passive"))
    )
    (net (code "45") (name "Net-(D3-C1A2)") (class "Default")
      (node (ref "C14") (pin "2") (pinfunction "2_2") (pintype "passive"))
      (node (ref "D3") (pin "3") (pinfunction "C1A2_3") (pintype "passive"))
    )
    (net (code "46") (name "Net-(D5-PadA)") (class "Default")
      (node (ref "D5") (pin "A") (pinfunction "A_A") (pintype "passive"))
      (node (ref "R23") (pin "1") (pinfunction "1_1") (pintype "passive"))
    )
    (net (code "47") (name "Net-(D6-PadA)") (class "Default")
      (node (ref "D6") (pin "A") (pinfunction "A_A") (pintype "passive"))
      (node (ref "R24") (pin "1") (pinfunction "1_1") (pintype "passive"))
    )
    (net (code "48") (name "Net-(D7-PadA)") (class "Default")
      (node (ref "D7") (pin "A") (pinfunction "A_A") (pintype "passive"))
      (node (ref "R25") (pin "1") (pinfunction "1_1") (pintype "passive"))
    )
    (net (code "49") (name "Net-(D8-PadA)") (class "Default")
      (node (ref "D8") (pin "A") (pinfunction "A_A") (pintype "passive"))
      (node (ref "R26") (pin "1") (pinfunction "1_1") (pintype "passive"))
    )
    (net (code "50") (name "Net-(Q3-G)") (class "Default")
      (node (ref "Q3") (pin "1") (pinfunction "G_1") (pintype "passive"))
      (node (ref "R12") (pin "1") (pinfunction "1_1") (pintype "passive"))
      (node (ref "R13") (pin "1") (pinfunction "1_1") (pintype "passive"))
    )
    (net (code "51") (name "Net-(Q4-D)") (class "Default")
      (node (ref "Q4") (pin "3") (pinfunction "D_3") (pintype "passive"))
      (node (ref "R13") (pin "2") (pinfunction "2_2") (pintype "passive"))
    )
    (net (code "52") (name "Net-(Q5-D)") (class "Default")
      (node (ref "C20") (pin "2") (pinfunction "2_2") (pintype "passive"))
      (node (ref "Q5") (pin "3") (pinfunction "D_3") (pintype "passive"))
      (node (ref "R17") (pin "1") (pinfunction "1_1") (pintype "passive"))
      (node (ref "U$10") (pin "1") (pinfunction "GATE_1") (pintype "bidirectional"))
    )
    (net (code "53") (name "Net-(Q7-D)") (class "Default")
      (node (ref "Q7") (pin "3") (pinfunction "D_3") (pintype "passive"))
      (node (ref "R17") (pin "2") (pinfunction "2_2") (pintype "passive"))
    )
    (net (code "54") (name "Net-(R7-Pad2)") (class "Default")
      (node (ref "R7") (pin "2") (pinfunction "2_2") (pintype "passive"))
      (node (ref "U$4") (pin "1") (pinfunction "A_1") (pintype "bidirectional"))
      (node (ref "U$4") (pin "1'") (pinfunction "A_1'") (pintype "bidirectional"))
    )
    (net (code "55") (name "Net-(R8-Pad2)") (class "Default")
      (node (ref "R8") (pin "2") (pinfunction "2_2") (pintype "passive"))
      (node (ref "U$5") (pin "1") (pinfunction "A_1") (pintype "bidirectional"))
      (node (ref "U$5") (pin "1'") (pinfunction "A_1'") (pintype "bidirectional"))
    )
    (net (code "56") (name "Net-(R9-Pad2)") (class "Default")
      (node (ref "R9") (pin "2") (pinfunction "2_2") (pintype "passive"))
      (node (ref "U$6") (pin "1") (pinfunction "A_1") (pintype "bidirectional"))
      (node (ref "U$6") (pin "1'") (pinfunction "A_1'") (pintype "bidirectional"))
    )
    (net (code "57") (name "Net-(R10-Pad2)") (class "Default")
      (node (ref "R10") (pin "2") (pinfunction "2_2") (pintype "passive"))
      (node (ref "U$7") (pin "1") (pinfunction "A_1") (pintype "bidirectional"))
      (node (ref "U$7") (pin "1'") (pinfunction "A_1'") (pintype "bidirectional"))
    )
    (net (code "58") (name "Net-(U$1-VCORE)") (class "Default")
      (node (ref "C30") (pin "2") (pinfunction "2_2") (pintype "passive"))
      (node (ref "U$1") (pin "17") (pinfunction "VCORE_17") (pintype "bidirectional"))
    )
    (net (code "59") (name "Net-(U$3-EN)") (class "Default")
      (node (ref "R6") (pin "1") (pinfunction "1_1") (pintype "passive"))
      (node (ref "U$3") (pin "4") (pinfunction "EN_4") (pintype "bidirectional"))
    )
    (net (code "60") (name "Net-(U$3-FB)") (class "Default")
      (node (ref "R1") (pin "1") (pinfunction "1_1") (pintype "passive"))
      (node (ref "R2") (pin "2") (pinfunction "2_2") (pintype "passive"))
      (node (ref "U$3") (pin "2") (pinfunction "FB_2") (pintype "bidirectional"))
    )
    (net (code "61") (name "Net-(U$3-ISET1)") (class "Default")
      (node (ref "R5") (pin "1") (pinfunction "1_1") (pintype "passive"))
      (node (ref "U$3") (pin "12") (pinfunction "ISET1_12") (pintype "bidirectional"))
    )
    (net (code "62") (name "Net-(U$3-ISET2)") (class "Default")
      (node (ref "D9") (pin "C") (pinfunction "C_C") (pintype "passive"))
      (node (ref "U$3") (pin "13") (pinfunction "ISET2_13") (pintype "bidirectional"))
    )
    (net (code "63") (name "Net-(U$3-STAT1)") (class "Default")
      (node (ref "R4") (pin "1") (pinfunction "1_1") (pintype "passive"))
      (node (ref "U$3") (pin "7") (pinfunction "STAT1_7") (pintype "bidirectional"))
    )
    (net (code "64") (name "Net-(U$3-STAT2)") (class "Default")
      (node (ref "R3") (pin "1") (pinfunction "1_1") (pintype "passive"))
      (node (ref "U$3") (pin "8") (pinfunction "STAT2_8") (pintype "bidirectional"))
    )
    (net (code "65") (name "Net-(U$8-C11M)") (class "Default")
      (node (ref "C13") (pin "1") (pinfunction "1_1") (pintype "passive"))
      (node (ref "U$8") (pin "28") (pinfunction "C11M_28") (pintype "bidirectional"))
    )
    (net (code "66") (name "Net-(U$8-C11P)") (class "Default")
      (node (ref "C13") (pin "2") (pinfunction "2_2") (pintype "passive"))
      (node (ref "U$8") (pin "29") (pinfunction "C11P_29") (pintype "bidirectional"))
    )
    (net (code "67") (name "Net-(U$8-C12M)") (class "Default")
      (node (ref "C12") (pin "1") (pinfunction "1_1") (pintype "passive"))
      (node (ref "U$8") (pin "26") (pinfunction "C12M_26") (pintype "bidirectional"))
    )
    (net (code "68") (name "Net-(U$8-C12P)") (class "Default")
      (node (ref "C12") (pin "2") (pinfunction "2_2") (pintype "passive"))
      (node (ref "U$8") (pin "27") (pinfunction "C12P_27") (pintype "bidirectional"))
    )
    (net (code "69") (name "Net-(U$8-C13M)") (class "Default")
      (node (ref "C11") (pin "1") (pinfunction "1_1") (pintype "passive"))
      (node (ref "U$8") (pin "24") (pinfunction "C13M_24") (pintype "bidirectional"))
    )
    (net (code "70") (name "Net-(U$8-C13P)") (class "Default")
      (node (ref "C11") (pin "2") (pinfunction "2_2") (pintype "passive"))
      (node (ref "U$8") (pin "25") (pinfunction "C13P_25") (pintype "bidirectional"))
    )
    (net (code "71") (name "Net-(U$8-C14M)") (class "Default")
      (node (ref "C10") (pin "1") (pinfunction "1_1") (pintype "passive"))
      (node (ref "U$8") (pin "22") (pinfunction "C14M_22") (pintype "bidirectional"))
    )
    (net (code "72") (name "Net-(U$8-C14P)") (class "Default")
      (node (ref "C10") (pin "2") (pinfunction "2_2") (pintype "passive"))
      (node (ref "U$8") (pin "23") (pinfunction "C14P_23") (pintype "bidirectional"))
    )
    (net (code "73") (name "Net-(U$8-C15M)") (class "Default")
      (node (ref "C9") (pin "1") (pinfunction "1_1") (pintype "passive"))
      (node (ref "U$8") (pin "20") (pinfunction "C15M_20") (pintype "bidirectional"))
    )
    (net (code "74") (name "Net-(U$8-C15P)") (class "Default")
      (node (ref "C9") (pin "2") (pinfunction "2_2") (pintype "passive"))
      (node (ref "U$8") (pin "21") (pinfunction "C15P_21") (pintype "bidirectional"))
    )
    (net (code "75") (name "Net-(U$8-C16M)") (class "Default")
      (node (ref "C8") (pin "2") (pinfunction "2_2") (pintype "passive"))
      (node (ref "U$8") (pin "18") (pinfunction "C16M_18") (pintype "bidirectional"))
    )
    (net (code "76") (name "Net-(U$8-C16P)") (class "Default")
      (node (ref "C8") (pin "1") (pinfunction "1_1") (pintype "passive"))
      (node (ref "U$8") (pin "19") (pinfunction "C16P_19") (pintype "bidirectional"))
    )
    (net (code "77") (name "Net-(U$8-C21M)") (class "Default")
      (node (ref "C7") (pin "2") (pinfunction "2_2") (pintype "passive"))
      (node (ref "U$8") (pin "16") (pinfunction "C21M_16") (pintype "bidirectional"))
    )
    (net (code "78") (name "Net-(U$8-C21P)") (class "Default")
      (node (ref "C7") (pin "1") (pinfunction "1_1") (pintype "passive"))
      (node (ref "U$8") (pin "17") (pinfunction "C21P_17") (pintype "bidirectional"))
    )
    (net (code "79") (name "Net-(U$8-C31M)") (class "Default")
      (node (ref "C6") (pin "2") (pinfunction "2_2") (pintype "passive"))
      (node (ref "U$8") (pin "14") (pinfunction "C31M_14") (pintype "bidirectional"))
    )
    (net (code "80") (name "Net-(U$8-C31P)") (class "Default")
      (node (ref "C6") (pin "1") (pinfunction "1_1") (pintype "passive"))
      (node (ref "U$8") (pin "15") (pinfunction "C31P_15") (pintype "bidirectional"))
    )
    (net (code "81") (name "Net-(U$8-C41M)") (class "Default")
      (node (ref "C5") (pin "1") (pinfunction "1_1") (pintype "passive"))
      (node (ref "U$8") (pin "13") (pinfunction "C41M_13") (pintype "bidirectional"))
    )
    (net (code "82") (name "Net-(U$8-C41P)") (class "Default")
      (node (ref "C5") (pin "2") (pinfunction "2_2") (pintype "passive"))
      (node (ref "U$8") (pin "12") (pinfunction "C41P_12") (pintype "bidirectional"))
    )
    (net (code "83") (name "Net-(U$8-C42M)") (class "Default")
      (node (ref "C4") (pin "1") (pinfunction "1_1") (pintype "passive"))
      (node (ref "U$8") (pin "11") (pinfunction "C42M_11") (pintype "bidirectional"))
    )
    (net (code "84") (name "Net-(U$8-C42P)") (class "Default")
      (node (ref "C4") (pin "2") (pinfunction "2_2") (pintype "passive"))
      (node (ref "U$8") (pin "10") (pinfunction "C42P_10") (pintype "bidirectional"))
    )
    (net (code "85") (name "Net-(U$8-VCL)") (class "Default")
      (node (ref "C3") (pin "2") (pinfunction "2_2") (pintype "passive"))
      (node (ref "U$8") (pin "9") (pinfunction "VCL_9") (pintype "bidirectional"))
    )
    (net (code "86") (name "Net-(U$9-SRP)") (class "Default")
      (node (ref "C23") (pin "1") (pinfunction "1_1") (pintype "passive"))
      (node (ref "R18") (pin "1") (pinfunction "1_1") (pintype "passive"))
      (node (ref "U$9") (pin "7") (pinfunction "SRP_7") (pintype "bidirectional"))
    )
    (net (code "87") (name "Net-(U$10-DRAIN)") (class "Default")
      (node (ref "R15") (pin "1") (pinfunction "1_1") (pintype "passive"))
      (node (ref "U$10") (pin "3") (pinfunction "DRAIN_3") (pintype "bidirectional"))
    )
    (net (code "88") (name "Net-(U$11-P$1)") (class "Default")
      (node (ref "U$11") (pin "1") (pinfunction "P$1_1") (pintype "bidirectional"))
      (node (ref "U$3") (pin "19") (pinfunction "SW_19") (pintype "bidirectional"))
    )
    (net (code "89") (name "unconnected-(U$1-P1.0{slash}TA0CLK{slash}ACLK-Pad18)") (class "Default")
      (node (ref "U$1") (pin "18") (pinfunction "P1.0/TA0CLK/ACLK_18") (pintype "bidirectional"))
    )
    (net (code "90") (name "unconnected-(U$1-P1.2{slash}TA0.1-Pad20)") (class "Default")
      (node (ref "U$1") (pin "20") (pinfunction "P1.2/TA0.1_20") (pintype "bidirectional"))
    )
    (net (code "91") (name "unconnected-(U$1-P1.3{slash}TA0.2-Pad21)") (class "Default")
      (node (ref "U$1") (pin "21") (pinfunction "P1.3/TA0.2_21") (pintype "bidirectional"))
    )
    (net (code "92") (name "unconnected-(U$1-P1.4{slash}TA0.3-Pad22)") (class "Default")
      (node (ref "U$1") (pin "22") (pinfunction "P1.4/TA0.3_22") (pintype "bidirectional"))
    )
    (net (code "93") (name "unconnected-(U$1-P1.5{slash}TA0.4-Pad23)") (class "Default")
      (node (ref "U$1") (pin "23") (pinfunction "P1.5/TA0.4_23") (pintype "bidirectional"))
    )
    (net (code "94") (name "unconnected-(U$1-P1.6{slash}TA1CLK{slash}CNOUT-Pad24)") (class "Default")
      (node (ref "U$1") (pin "24") (pinfunction "P1.6/TA1CLK/CNOUT_24") (pintype "bidirectional"))
    )
    (net (code "95") (name "unconnected-(U$1-P1.7{slash}TA1.0-Pad25)") (class "Default")
      (node (ref "U$1") (pin "25") (pinfunction "P1.7/TA1.0_25") (pintype "bidirectional"))
    )
    (net (code "96") (name "unconnected-(U$1-P3.4{slash}UCA0RXD{slash}UCA0SOMI-Pad38)") (class "Default")
      (node (ref "U$1") (pin "38") (pinfunction "P3.4/UCA0RXD/UCA0SOMI_38") (pintype "bidirectional"))
    )
    (net (code "97") (name "unconnected-(U$1-P4.0{slash}PM_UCB1STE{slash}PM_UCA1CLK-Pad41)") (class "Default")
      (node (ref "U$1") (pin "41") (pinfunction "P4.0/PM_UCB1STE/PM_UCA1CLK_41") (pintype "bidirectional"))
    )
    (net (code "98") (name "unconnected-(U$1-P5.0{slash}A8{slash}VREF+-Pad9)") (class "Default")
      (node (ref "U$1") (pin "9") (pinfunction "P5.0/A8/VREF+_9") (pintype "bidirectional"))
    )
    (net (code "99") (name "unconnected-(U$1-P5.1{slash}A9{slash}VREF--Pad10)") (class "Default")
      (node (ref "U$1") (pin "10") (pinfunction "P5.1/A9/VREF-_10") (pintype "bidirectional"))
    )
    (net (code "100") (name "unconnected-(U$1-P5.2{slash}XT2IN-Pad57)") (class "Default")
      (node (ref "U$1") (pin "57") (pinfunction "P5.2/XT2IN_57") (pintype "bidirectional"))
    )
    (net (code "101") (name "unconnected-(U$1-P5.3{slash}XT2OUT-Pad58)") (class "Default")
      (node (ref "U$1") (pin "58") (pinfunction "P5.3/XT2OUT_58") (pintype "bidirectional"))
    )
    (net (code "102") (name "unconnected-(U$1-P5.4{slash}XIN-Pad12)") (class "Default")
      (node (ref "U$1") (pin "12") (pinfunction "P5.4/XIN_12") (pintype "bidirectional"))
    )
    (net (code "103") (name "unconnected-(U$1-P5.5{slash}XOUT-Pad13)") (class "Default")
      (node (ref "U$1") (pin "13") (pinfunction "P5.5/XOUT_13") (pintype "bidirectional"))
    )
    (net (code "104") (name "unconnected-(U$1-PJ.0{slash}TDO-Pad60)") (class "Default")
      (node (ref "U$1") (pin "60") (pinfunction "PJ.0/TDO_60") (pintype "bidirectional"))
    )
    (net (code "105") (name "unconnected-(U$1-PJ.1{slash}TDI{slash}TCLK-Pad61)") (class "Default")
      (node (ref "U$1") (pin "61") (pinfunction "PJ.1/TDI/TCLK_61") (pintype "bidirectional"))
    )
    (net (code "106") (name "unconnected-(U$1-PJ.2{slash}TMS-Pad62)") (class "Default")
      (node (ref "U$1") (pin "62") (pinfunction "PJ.2/TMS_62") (pintype "bidirectional"))
    )
    (net (code "107") (name "unconnected-(U$1-PJ.3{slash}TCK-Pad63)") (class "Default")
      (node (ref "U$1") (pin "63") (pinfunction "PJ.3/TCK_63") (pintype "bidirectional"))
    )
    (net (code "108") (name "unconnected-(U$1-PU.0{slash}DP-Pad50)") (class "Default")
      (node (ref "U$1") (pin "50") (pinfunction "PU.0/DP_50") (pintype "bidirectional"))
    )
    (net (code "109") (name "unconnected-(U$1-PU.1{slash}DM-Pad52)") (class "Default")
      (node (ref "U$1") (pin "52") (pinfunction "PU.1/DM_52") (pintype "bidirectional"))
    )
    (net (code "110") (name "unconnected-(U$1-PUR-Pad51)") (class "Default")
      (node (ref "U$1") (pin "51") (pinfunction "PUR_51") (pintype "bidirectional"))
    )
    (net (code "111") (name "unconnected-(U$1-V18-Pad55)") (class "Default")
      (node (ref "U$1") (pin "55") (pinfunction "V18_55") (pintype "bidirectional"))
    )
    (net (code "112") (name "unconnected-(U$1-VBUS-Pad53)") (class "Default")
      (node (ref "U$1") (pin "53") (pinfunction "VBUS_53") (pintype "bidirectional"))
    )
    (net (code "113") (name "unconnected-(U$1-VUSB-Pad54)") (class "Default")
      (node (ref "U$1") (pin "54") (pinfunction "VUSB_54") (pintype "bidirectional"))
    )
    (net (code "114") (name "unconnected-(U$2-AIO0-Pad30)") (class "Default")
      (node (ref "U$2") (pin "30") (pinfunction "AIO0_30") (pintype "bidirectional"))
    )
    (net (code "115") (name "unconnected-(U$2-AIO1-Pad35)") (class "Default")
      (node (ref "U$2") (pin "35") (pinfunction "AIO1_35") (pintype "bidirectional"))
    )
    (net (code "116") (name "unconnected-(U$2-PCM_CLK-Pad7)") (class "Default")
      (node (ref "U$2") (pin "7") (pinfunction "PCM_CLK_7") (pintype "bidirectional"))
    )
    (net (code "117") (name "unconnected-(U$2-PCM_IN-Pad9)") (class "Default")
      (node (ref "U$2") (pin "9") (pinfunction "PCM_IN_9") (pintype "bidirectional"))
    )
    (net (code "118") (name "unconnected-(U$2-PCM_OUT-Pad10)") (class "Default")
      (node (ref "U$2") (pin "10") (pinfunction "PCM_OUT_10") (pintype "bidirectional"))
    )
    (net (code "119") (name "unconnected-(U$2-PCM_SYNC-Pad8)") (class "Default")
      (node (ref "U$2") (pin "8") (pinfunction "PCM_SYNC_8") (pintype "bidirectional"))
    )
    (net (code "120") (name "unconnected-(U$2-PIO3-Pad20)") (class "Default")
      (node (ref "U$2") (pin "20") (pinfunction "PIO3_20") (pintype "bidirectional"))
    )
    (net (code "121") (name "unconnected-(U$2-PIO4-Pad22)") (class "Default")
      (node (ref "U$2") (pin "22") (pinfunction "PIO4_22") (pintype "bidirectional"))
    )
    (net (code "122") (name "unconnected-(U$2-PIO5-Pad21)") (class "Default")
      (node (ref "U$2") (pin "21") (pinfunction "PIO5_21") (pintype "bidirectional"))
    )
    (net (code "123") (name "unconnected-(U$2-PIO6-Pad3)") (class "Default")
      (node (ref "U$2") (pin "3") (pinfunction "PIO6_3") (pintype "bidirectional"))
    )
    (net (code "124") (name "unconnected-(U$2-PIO8-Pad31)") (class "Default")
      (node (ref "U$2") (pin "31") (pinfunction "PIO8_31") (pintype "bidirectional"))
    )
    (net (code "125") (name "unconnected-(U$2-PIO9-Pad32)") (class "Default")
      (node (ref "U$2") (pin "32") (pinfunction "PIO9_32") (pintype "bidirectional"))
    )
    (net (code "126") (name "unconnected-(U$2-PIO10-Pad33)") (class "Default")
      (node (ref "U$2") (pin "33") (pinfunction "PIO10_33") (pintype "bidirectional"))
    )
    (net (code "127") (name "unconnected-(U$2-PIO11-Pad34)") (class "Default")
      (node (ref "U$2") (pin "34") (pinfunction "PIO11_34") (pintype "bidirectional"))
    )
    (net (code "128") (name "unconnected-(U$2-RST-Pad5)") (class "Default")
      (node (ref "U$2") (pin "5") (pinfunction "RST_5") (pintype "bidirectional"))
    )
    (net (code "129") (name "unconnected-(U$2-SPI_CLK-Pad6)") (class "Default")
      (node (ref "U$2") (pin "6") (pinfunction "SPI_CLK_6") (pintype "bidirectional"))
    )
    (net (code "130") (name "unconnected-(U$2-SPI_CSB-Pad23)") (class "Default")
      (node (ref "U$2") (pin "23") (pinfunction "SPI_CSB_23") (pintype "bidirectional"))
    )
    (net (code "131") (name "unconnected-(U$2-SPI_MISO-Pad24)") (class "Default")
      (node (ref "U$2") (pin "24") (pinfunction "SPI_MISO_24") (pintype "bidirectional"))
    )
    (net (code "132") (name "unconnected-(U$2-SPI_MOSI-Pad2)") (class "Default")
      (node (ref "U$2") (pin "2") (pinfunction "SPI_MOSI_2") (pintype "bidirectional"))
    )
    (net (code "133") (name "unconnected-(U$2-UART_RTS-Pad15)") (class "Default")
      (node (ref "U$2") (pin "15") (pinfunction "UART_RTS_15") (pintype "bidirectional"))
    )
    (net (code "134") (name "unconnected-(U$2-USART_CTS-Pad16)") (class "Default")
      (node (ref "U$2") (pin "16") (pinfunction "USART_CTS_16") (pintype "bidirectional"))
    )
    (net (code "135") (name "unconnected-(U$2-USB_D+-Pad17)") (class "Default")
      (node (ref "U$2") (pin "17") (pinfunction "USB_D+_17") (pintype "bidirectional"))
    )
    (net (code "136") (name "unconnected-(U$2-USB_D--Pad18)") (class "Default")
      (node (ref "U$2") (pin "18") (pinfunction "USB_D-_18") (pintype "bidirectional"))
    )
    (net (code "137") (name "unconnected-(U$3-AC-Pad5)") (class "Default")
      (node (ref "U$3") (pin "5") (pinfunction "AC_5") (pintype "bidirectional"))
    )
    (net (code "138") (name "unconnected-(U$3-PG-Pad14)") (class "Default")
      (node (ref "U$3") (pin "14") (pinfunction "PG_14") (pintype "bidirectional"))
    )
    (net (code "139") (name "unconnected-(U$8-ADC_IN-Pad8)") (class "Default")
      (node (ref "U$8") (pin "8") (pinfunction "ADC_IN_8") (pintype "bidirectional"))
    )
  )
)
